# TubeBoard.net
KiCad netlist of a schematic drawn in EAGLE
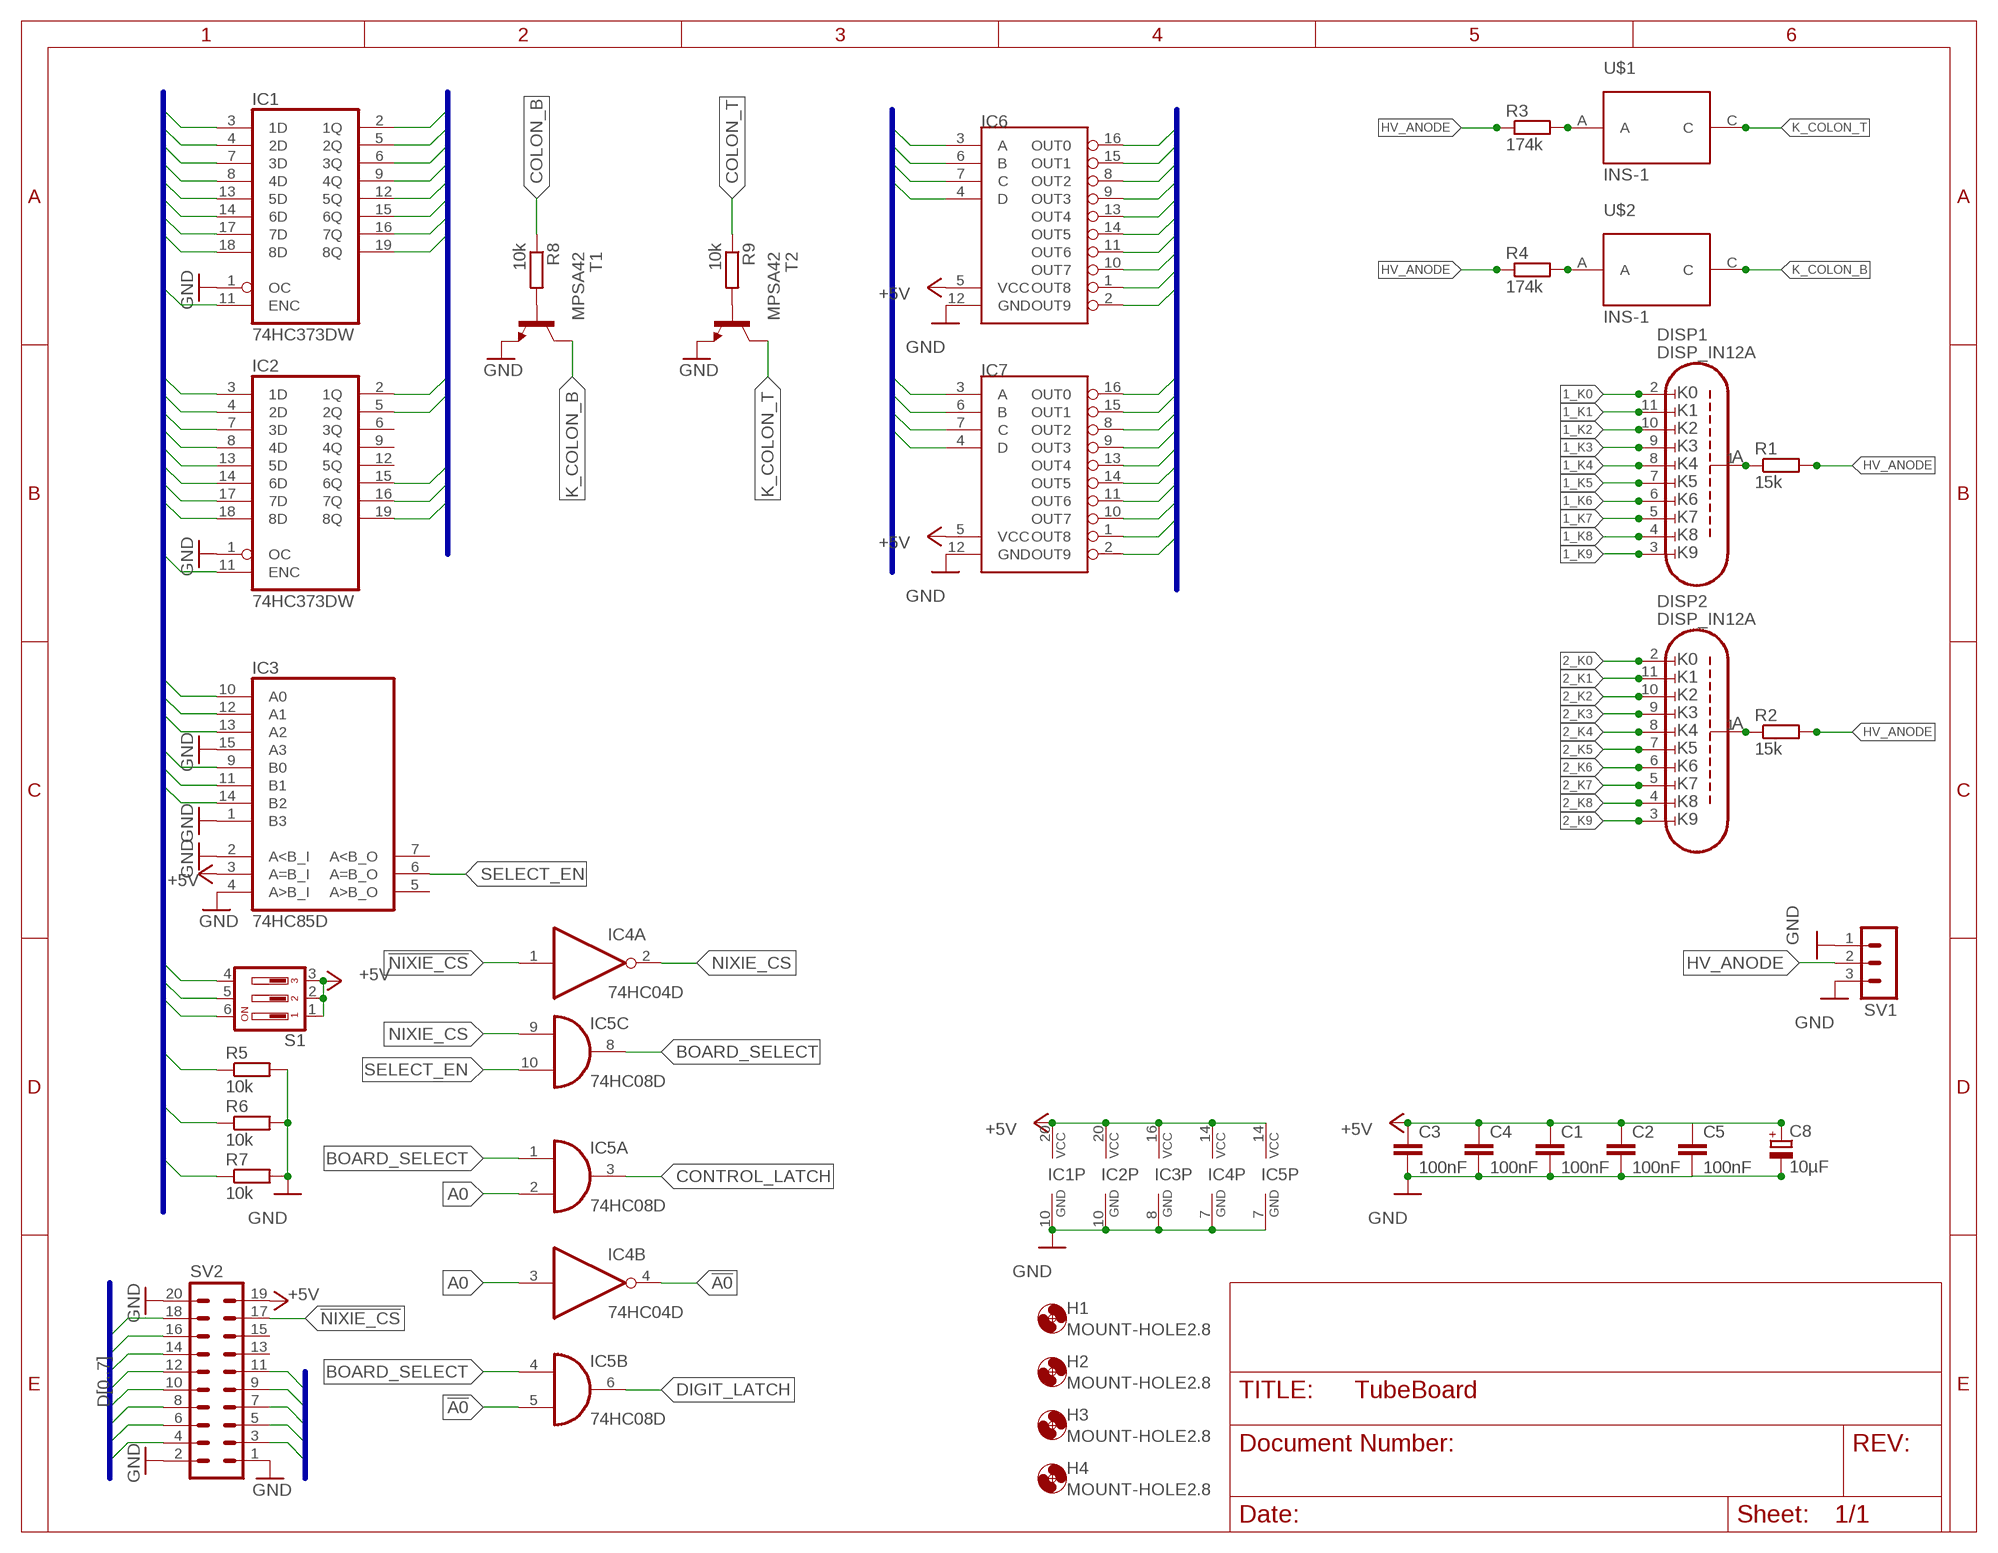
[diagram p0: schematic, sheet 1]

(export (version "E")
  (design (tool "Eeschema 10.0.6"))
  (components
    (comp (ref "C1")
      (value "100nF")
      (footprint "eagle-import:C1206")
      (libsource (lib "eagle-import") (part "C-EUC1206"))
    )
    (comp (ref "C2")
      (value "100nF")
      (footprint "eagle-import:C1206")
      (libsource (lib "eagle-import") (part "C-EUC1206"))
    )
    (comp (ref "C3")
      (value "100nF")
      (footprint "eagle-import:C1206")
      (libsource (lib "eagle-import") (part "C-EUC1206"))
    )
    (comp (ref "C4")
      (value "100nF")
      (footprint "eagle-import:C1206")
      (libsource (lib "eagle-import") (part "C-EUC1206"))
    )
    (comp (ref "C5")
      (value "100nF")
      (footprint "eagle-import:C1206")
      (libsource (lib "eagle-import") (part "C-EUC1206"))
    )
    (comp (ref "C8")
      (value "10µF")
      (footprint "eagle-import:SMC_B")
      (libsource (lib "eagle-import") (part "CPOL-EUSMCB"))
    )
    (comp (ref "DISP1")
      (value "DISP_IN12A")
      (footprint "eagle-import:DISP_IN-12_SOCKET")
      (libsource (lib "eagle-import") (part "DISP_IN12A"))
    )
    (comp (ref "DISP2")
      (value "DISP_IN12A")
      (footprint "eagle-import:DISP_IN-12_SOCKET")
      (libsource (lib "eagle-import") (part "DISP_IN12A"))
    )
    (comp (ref "H1")
      (value "MOUNT-HOLE2.8")
      (footprint "eagle-import:2,8")
      (libsource (lib "eagle-import") (part "MOUNT-HOLE2.8"))
    )
    (comp (ref "H2")
      (value "MOUNT-HOLE2.8")
      (footprint "eagle-import:2,8")
      (libsource (lib "eagle-import") (part "MOUNT-HOLE2.8"))
    )
    (comp (ref "H3")
      (value "MOUNT-HOLE2.8")
      (footprint "eagle-import:2,8")
      (libsource (lib "eagle-import") (part "MOUNT-HOLE2.8"))
    )
    (comp (ref "H4")
      (value "MOUNT-HOLE2.8")
      (footprint "eagle-import:2,8")
      (libsource (lib "eagle-import") (part "MOUNT-HOLE2.8"))
    )
    (comp (ref "IC1")
      (value "74HC373DW")
      (footprint "eagle-import:SO20W")
      (libsource (lib "eagle-import") (part "74373DWHC"))
    )
    (comp (ref "IC2")
      (value "74HC373DW")
      (footprint "eagle-import:SO20W")
      (libsource (lib "eagle-import") (part "74373DWHC"))
    )
    (comp (ref "IC3")
      (value "74HC85D")
      (footprint "eagle-import:SO16")
      (fields (field (name "MOUSER") "771-74HC85D-T"))
      (libsource (lib "eagle-import") (part "7485DHC"))
    )
    (comp (ref "IC4")
      (value "74HC04D")
      (footprint "eagle-import:SO14")
      (libsource (lib "eagle-import") (part "7404DHC"))
    )
    (comp (ref "IC5")
      (value "74HC08D")
      (footprint "eagle-import:SO14")
      (libsource (lib "eagle-import") (part "7408DHC"))
    )
    (comp (ref "IC6")
      (value "7441DIL16")
      (footprint "eagle-import:DIL16")
      (libsource (lib "eagle-import") (part "7441DIL16"))
    )
    (comp (ref "IC7")
      (value "7441DIL16")
      (footprint "eagle-import:DIL16")
      (libsource (lib "eagle-import") (part "7441DIL16"))
    )
    (comp (ref "R1")
      (value "15k")
      (footprint "eagle-import:0411_12")
      (libsource (lib "eagle-import") (part "R-EU_0411/12"))
    )
    (comp (ref "R2")
      (value "15k")
      (footprint "eagle-import:0411_12")
      (libsource (lib "eagle-import") (part "R-EU_0411/12"))
    )
    (comp (ref "R3")
      (value "174k")
      (footprint "eagle-import:M1206")
      (libsource (lib "eagle-import") (part "R-EU_M1206"))
    )
    (comp (ref "R4")
      (value "174k")
      (footprint "eagle-import:M1206")
      (libsource (lib "eagle-import") (part "R-EU_M1206"))
    )
    (comp (ref "R5")
      (value "10k")
      (footprint "eagle-import:R2012")
      (libsource (lib "eagle-import") (part "R-EU_R2012"))
    )
    (comp (ref "R6")
      (value "10k")
      (footprint "eagle-import:R2012")
      (libsource (lib "eagle-import") (part "R-EU_R2012"))
    )
    (comp (ref "R7")
      (value "10k")
      (footprint "eagle-import:R2012")
      (libsource (lib "eagle-import") (part "R-EU_R2012"))
    )
    (comp (ref "R8")
      (value "10k")
      (footprint "eagle-import:R2012")
      (libsource (lib "eagle-import") (part "R-EU_R2012"))
    )
    (comp (ref "R9")
      (value "10k")
      (footprint "eagle-import:R2012")
      (libsource (lib "eagle-import") (part "R-EU_R2012"))
    )
    (comp (ref "S1")
      (value "SD4-03")
      (footprint "eagle-import:SD4-03")
      (libsource (lib "eagle-import") (part "SD4-03"))
    )
    (comp (ref "SV1")
      (value "MA03-1")
      (footprint "eagle-import:MA03-1")
      (libsource (lib "eagle-import") (part "MA03-1"))
    )
    (comp (ref "SV2")
      (value "MA10-2")
      (footprint "eagle-import:MA10-2")
      (libsource (lib "eagle-import") (part "MA10-2"))
    )
    (comp (ref "T1")
      (value "MPSA42")
      (footprint "eagle-import:TO92-EBC")
      (libsource (lib "eagle-import") (part "-NPN-TO92-EBCMPSA42"))
    )
    (comp (ref "T2")
      (value "MPSA42")
      (footprint "eagle-import:TO92-EBC")
      (libsource (lib "eagle-import") (part "-NPN-TO92-EBCMPSA42"))
    )
    (comp (ref "U$1")
      (value "INS-1")
      (footprint "eagle-import:INS-1")
      (libsource (lib "eagle-import") (part "INS-1"))
    )
    (comp (ref "U$2")
      (value "INS-1")
      (footprint "eagle-import:INS-1")
      (libsource (lib "eagle-import") (part "INS-1"))
    )
  )
  (nets
    (net (code "1") (name "+5V") (class "Default")
      (node (ref "C1") (pin "1") (pinfunction "1_1") (pintype "passive"))
      (node (ref "C2") (pin "1") (pinfunction "1_1") (pintype "passive"))
      (node (ref "C3") (pin "1") (pinfunction "1_1") (pintype "passive"))
      (node (ref "C4") (pin "1") (pinfunction "1_1") (pintype "passive"))
      (node (ref "C5") (pin "1") (pinfunction "1_1") (pintype "passive"))
      (node (ref "C8") (pin "+") (pinfunction "+_+") (pintype "passive"))
      (node (ref "IC1") (pin "20") (pinfunction "VCC_20") (pintype "power_in"))
      (node (ref "IC2") (pin "20") (pinfunction "VCC_20") (pintype "power_in"))
      (node (ref "IC3") (pin "16") (pinfunction "VCC_16") (pintype "power_in"))
      (node (ref "IC3") (pin "3") (pinfunction "A=B_I_3") (pintype "input"))
      (node (ref "IC4") (pin "14") (pinfunction "VCC_14") (pintype "power_in"))
      (node (ref "IC5") (pin "14") (pinfunction "VCC_14") (pintype "power_in"))
      (node (ref "IC6") (pin "5") (pinfunction "VCC_5") (pintype "passive"))
      (node (ref "IC7") (pin "5") (pinfunction "VCC_5") (pintype "passive"))
      (node (ref "S1") (pin "1") (pinfunction "1_1") (pintype "passive"))
      (node (ref "S1") (pin "2") (pinfunction "2_2") (pintype "passive"))
      (node (ref "S1") (pin "3") (pinfunction "3_3") (pintype "passive"))
      (node (ref "SV2") (pin "19") (pinfunction "19_19") (pintype "passive"))
    )
    (net (code "2") (name "/A2") (class "Default")
      (node (ref "IC3") (pin "10") (pinfunction "A0_10") (pintype "input"))
      (node (ref "SV2") (pin "7") (pinfunction "7_7") (pintype "passive"))
    )
    (net (code "3") (name "/A3") (class "Default")
      (node (ref "IC3") (pin "12") (pinfunction "A1_12") (pintype "input"))
      (node (ref "SV2") (pin "9") (pinfunction "9_9") (pintype "passive"))
    )
    (net (code "4") (name "/A4") (class "Default")
      (node (ref "IC3") (pin "13") (pinfunction "A2_13") (pintype "input"))
      (node (ref "SV2") (pin "11") (pinfunction "11_11") (pintype "passive"))
    )
    (net (code "5") (name "/D0") (class "Default")
      (node (ref "IC1") (pin "3") (pinfunction "1D_3") (pintype "input"))
      (node (ref "IC2") (pin "3") (pinfunction "1D_3") (pintype "input"))
      (node (ref "SV2") (pin "8") (pinfunction "8_8") (pintype "passive"))
    )
    (net (code "6") (name "/D1") (class "Default")
      (node (ref "IC1") (pin "4") (pinfunction "2D_4") (pintype "input"))
      (node (ref "IC2") (pin "4") (pinfunction "2D_4") (pintype "input"))
      (node (ref "SV2") (pin "6") (pinfunction "6_6") (pintype "passive"))
    )
    (net (code "7") (name "/D2") (class "Default")
      (node (ref "IC1") (pin "7") (pinfunction "3D_7") (pintype "input"))
      (node (ref "IC2") (pin "7") (pinfunction "3D_7") (pintype "input"))
      (node (ref "SV2") (pin "4") (pinfunction "4_4") (pintype "passive"))
    )
    (net (code "8") (name "/D3") (class "Default")
      (node (ref "IC1") (pin "8") (pinfunction "4D_8") (pintype "input"))
      (node (ref "IC2") (pin "8") (pinfunction "4D_8") (pintype "input"))
      (node (ref "SV2") (pin "10") (pinfunction "10_10") (pintype "passive"))
    )
    (net (code "9") (name "/D4") (class "Default")
      (node (ref "IC1") (pin "13") (pinfunction "5D_13") (pintype "input"))
      (node (ref "IC2") (pin "13") (pinfunction "5D_13") (pintype "input"))
      (node (ref "SV2") (pin "12") (pinfunction "12_12") (pintype "passive"))
    )
    (net (code "10") (name "/D5") (class "Default")
      (node (ref "IC1") (pin "14") (pinfunction "6D_14") (pintype "input"))
      (node (ref "IC2") (pin "14") (pinfunction "6D_14") (pintype "input"))
      (node (ref "SV2") (pin "14") (pinfunction "14_14") (pintype "passive"))
    )
    (net (code "11") (name "/D6") (class "Default")
      (node (ref "IC1") (pin "17") (pinfunction "7D_17") (pintype "input"))
      (node (ref "IC2") (pin "17") (pinfunction "7D_17") (pintype "input"))
      (node (ref "SV2") (pin "16") (pinfunction "16_16") (pintype "passive"))
    )
    (net (code "12") (name "/D7") (class "Default")
      (node (ref "IC1") (pin "18") (pinfunction "8D_18") (pintype "input"))
      (node (ref "IC2") (pin "18") (pinfunction "8D_18") (pintype "input"))
      (node (ref "SV2") (pin "18") (pinfunction "18_18") (pintype "passive"))
    )
    (net (code "14") (name "/ID0") (class "Default")
      (node (ref "IC3") (pin "9") (pinfunction "B0_9") (pintype "input"))
      (node (ref "R7") (pin "1") (pinfunction "1_1") (pintype "passive"))
      (node (ref "S1") (pin "6") (pinfunction "6_6") (pintype "passive"))
    )
    (net (code "15") (name "/ID1") (class "Default")
      (node (ref "IC3") (pin "11") (pinfunction "B1_11") (pintype "input"))
      (node (ref "R6") (pin "1") (pinfunction "1_1") (pintype "passive"))
      (node (ref "S1") (pin "5") (pinfunction "5_5") (pintype "passive"))
    )
    (net (code "16") (name "/ID2") (class "Default")
      (node (ref "IC3") (pin "14") (pinfunction "B2_14") (pintype "input"))
      (node (ref "R5") (pin "1") (pinfunction "1_1") (pintype "passive"))
      (node (ref "S1") (pin "4") (pinfunction "4_4") (pintype "passive"))
    )
    (net (code "17") (name "/LDIGIT0") (class "Default")
      (node (ref "IC1") (pin "2") (pinfunction "1Q_2") (pintype "tri_state"))
      (node (ref "IC6") (pin "3") (pinfunction "A_3") (pintype "input"))
    )
    (net (code "18") (name "/LDIGIT1") (class "Default")
      (node (ref "IC1") (pin "5") (pinfunction "2Q_5") (pintype "tri_state"))
      (node (ref "IC6") (pin "6") (pinfunction "B_6") (pintype "input"))
    )
    (net (code "19") (name "/LDIGIT2") (class "Default")
      (node (ref "IC1") (pin "6") (pinfunction "3Q_6") (pintype "tri_state"))
      (node (ref "IC6") (pin "7") (pinfunction "C_7") (pintype "input"))
    )
    (net (code "20") (name "/LDIGIT3") (class "Default")
      (node (ref "IC1") (pin "9") (pinfunction "4Q_9") (pintype "tri_state"))
      (node (ref "IC6") (pin "4") (pinfunction "D_4") (pintype "input"))
    )
    (net (code "21") (name "/RDIGIT0") (class "Default")
      (node (ref "IC1") (pin "12") (pinfunction "5Q_12") (pintype "tri_state"))
      (node (ref "IC7") (pin "3") (pinfunction "A_3") (pintype "input"))
    )
    (net (code "22") (name "/RDIGIT1") (class "Default")
      (node (ref "IC1") (pin "15") (pinfunction "6Q_15") (pintype "tri_state"))
      (node (ref "IC7") (pin "6") (pinfunction "B_6") (pintype "input"))
    )
    (net (code "23") (name "/RDIGIT2") (class "Default")
      (node (ref "IC1") (pin "16") (pinfunction "7Q_16") (pintype "tri_state"))
      (node (ref "IC7") (pin "7") (pinfunction "C_7") (pintype "input"))
    )
    (net (code "24") (name "/RDIGIT3") (class "Default")
      (node (ref "IC1") (pin "19") (pinfunction "8Q_19") (pintype "tri_state"))
      (node (ref "IC7") (pin "4") (pinfunction "D_4") (pintype "input"))
    )
    (net (code "25") (name "/~{A0}") (class "Default")
      (node (ref "IC4") (pin "4") (pinfunction "O_4") (pintype "output"))
      (node (ref "IC5") (pin "5") (pinfunction "I1_5") (pintype "input"))
    )
    (net (code "26") (name "/~{NIXIE_CS}") (class "Default")
      (node (ref "IC4") (pin "1") (pinfunction "I_1") (pintype "input"))
      (node (ref "SV2") (pin "17") (pinfunction "17_17") (pintype "passive"))
    )
    (net (code "27") (name "1_K0") (class "Default")
      (node (ref "DISP1") (pin "2") (pinfunction "K0_2") (pintype "input"))
      (node (ref "IC6") (pin "16") (pinfunction "OUT0_16") (pintype "output"))
    )
    (net (code "28") (name "1_K1") (class "Default")
      (node (ref "DISP1") (pin "11") (pinfunction "K1_11") (pintype "input"))
      (node (ref "IC6") (pin "15") (pinfunction "OUT1_15") (pintype "output"))
    )
    (net (code "29") (name "1_K2") (class "Default")
      (node (ref "DISP1") (pin "10") (pinfunction "K2_10") (pintype "input"))
      (node (ref "IC6") (pin "8") (pinfunction "OUT2_8") (pintype "output"))
    )
    (net (code "30") (name "1_K3") (class "Default")
      (node (ref "DISP1") (pin "9") (pinfunction "K3_9") (pintype "input"))
      (node (ref "IC6") (pin "9") (pinfunction "OUT3_9") (pintype "output"))
    )
    (net (code "31") (name "1_K4") (class "Default")
      (node (ref "DISP1") (pin "8") (pinfunction "K4_8") (pintype "input"))
      (node (ref "IC6") (pin "13") (pinfunction "OUT4_13") (pintype "output"))
    )
    (net (code "32") (name "1_K5") (class "Default")
      (node (ref "DISP1") (pin "7") (pinfunction "K5_7") (pintype "input"))
      (node (ref "IC6") (pin "14") (pinfunction "OUT5_14") (pintype "output"))
    )
    (net (code "33") (name "1_K6") (class "Default")
      (node (ref "DISP1") (pin "6") (pinfunction "K6_6") (pintype "input"))
      (node (ref "IC6") (pin "11") (pinfunction "OUT6_11") (pintype "output"))
    )
    (net (code "34") (name "1_K7") (class "Default")
      (node (ref "DISP1") (pin "5") (pinfunction "K7_5") (pintype "input"))
      (node (ref "IC6") (pin "10") (pinfunction "OUT7_10") (pintype "output"))
    )
    (net (code "35") (name "1_K8") (class "Default")
      (node (ref "DISP1") (pin "4") (pinfunction "K8_4") (pintype "input"))
      (node (ref "IC6") (pin "1") (pinfunction "OUT8_1") (pintype "output"))
    )
    (net (code "36") (name "1_K9") (class "Default")
      (node (ref "DISP1") (pin "3") (pinfunction "K9_3") (pintype "input"))
      (node (ref "IC6") (pin "2") (pinfunction "OUT9_2") (pintype "output"))
    )
    (net (code "37") (name "2_K0") (class "Default")
      (node (ref "DISP2") (pin "2") (pinfunction "K0_2") (pintype "input"))
      (node (ref "IC7") (pin "16") (pinfunction "OUT0_16") (pintype "output"))
    )
    (net (code "38") (name "2_K1") (class "Default")
      (node (ref "DISP2") (pin "11") (pinfunction "K1_11") (pintype "input"))
      (node (ref "IC7") (pin "15") (pinfunction "OUT1_15") (pintype "output"))
    )
    (net (code "39") (name "2_K2") (class "Default")
      (node (ref "DISP2") (pin "10") (pinfunction "K2_10") (pintype "input"))
      (node (ref "IC7") (pin "8") (pinfunction "OUT2_8") (pintype "output"))
    )
    (net (code "40") (name "2_K3") (class "Default")
      (node (ref "DISP2") (pin "9") (pinfunction "K3_9") (pintype "input"))
      (node (ref "IC7") (pin "9") (pinfunction "OUT3_9") (pintype "output"))
    )
    (net (code "41") (name "2_K4") (class "Default")
      (node (ref "DISP2") (pin "8") (pinfunction "K4_8") (pintype "input"))
      (node (ref "IC7") (pin "13") (pinfunction "OUT4_13") (pintype "output"))
    )
    (net (code "42") (name "2_K5") (class "Default")
      (node (ref "DISP2") (pin "7") (pinfunction "K5_7") (pintype "input"))
      (node (ref "IC7") (pin "14") (pinfunction "OUT5_14") (pintype "output"))
    )
    (net (code "43") (name "2_K6") (class "Default")
      (node (ref "DISP2") (pin "6") (pinfunction "K6_6") (pintype "input"))
      (node (ref "IC7") (pin "11") (pinfunction "OUT6_11") (pintype "output"))
    )
    (net (code "44") (name "2_K7") (class "Default")
      (node (ref "DISP2") (pin "5") (pinfunction "K7_5") (pintype "input"))
      (node (ref "IC7") (pin "10") (pinfunction "OUT7_10") (pintype "output"))
    )
    (net (code "45") (name "2_K8") (class "Default")
      (node (ref "DISP2") (pin "4") (pinfunction "K8_4") (pintype "input"))
      (node (ref "IC7") (pin "1") (pinfunction "OUT8_1") (pintype "output"))
    )
    (net (code "46") (name "2_K9") (class "Default")
      (node (ref "DISP2") (pin "3") (pinfunction "K9_3") (pintype "input"))
      (node (ref "IC7") (pin "2") (pinfunction "OUT9_2") (pintype "output"))
    )
    (net (code "47") (name "A0") (class "Default")
      (node (ref "IC4") (pin "3") (pinfunction "I_3") (pintype "input"))
      (node (ref "IC5") (pin "2") (pinfunction "I1_2") (pintype "input"))
      (node (ref "SV2") (pin "3") (pinfunction "3_3") (pintype "passive"))
    )
    (net (code "48") (name "BOARD_SELECT") (class "Default")
      (node (ref "IC5") (pin "1") (pinfunction "I0_1") (pintype "input"))
      (node (ref "IC5") (pin "4") (pinfunction "I0_4") (pintype "input"))
      (node (ref "IC5") (pin "8") (pinfunction "O_8") (pintype "output"))
    )
    (net (code "49") (name "COLON_B") (class "Default")
      (node (ref "IC2") (pin "2") (pinfunction "1Q_2") (pintype "tri_state"))
      (node (ref "R8") (pin "1") (pinfunction "1_1") (pintype "passive"))
    )
    (net (code "50") (name "COLON_T") (class "Default")
      (node (ref "IC2") (pin "5") (pinfunction "2Q_5") (pintype "tri_state"))
      (node (ref "R9") (pin "1") (pinfunction "1_1") (pintype "passive"))
    )
    (net (code "51") (name "CONTROL_LATCH") (class "Default")
      (node (ref "IC2") (pin "11") (pinfunction "ENC_11") (pintype "input"))
      (node (ref "IC5") (pin "3") (pinfunction "O_3") (pintype "output"))
    )
    (net (code "52") (name "DIGIT_LATCH") (class "Default")
      (node (ref "IC1") (pin "11") (pinfunction "ENC_11") (pintype "input"))
      (node (ref "IC5") (pin "6") (pinfunction "O_6") (pintype "output"))
    )
    (net (code "53") (name "GND") (class "Default")
      (node (ref "C1") (pin "2") (pinfunction "2_2") (pintype "passive"))
      (node (ref "C2") (pin "2") (pinfunction "2_2") (pintype "passive"))
      (node (ref "C3") (pin "2") (pinfunction "2_2") (pintype "passive"))
      (node (ref "C4") (pin "2") (pinfunction "2_2") (pintype "passive"))
      (node (ref "C5") (pin "2") (pinfunction "2_2") (pintype "passive"))
      (node (ref "C8") (pin "-") (pinfunction "-_-") (pintype "passive"))
      (node (ref "IC1") (pin "1") (pinfunction "OC_1") (pintype "input"))
      (node (ref "IC1") (pin "10") (pinfunction "GND_10") (pintype "power_in"))
      (node (ref "IC2") (pin "1") (pinfunction "OC_1") (pintype "input"))
      (node (ref "IC2") (pin "10") (pinfunction "GND_10") (pintype "power_in"))
      (node (ref "IC3") (pin "1") (pinfunction "B3_1") (pintype "input"))
      (node (ref "IC3") (pin "15") (pinfunction "A3_15") (pintype "input"))
      (node (ref "IC3") (pin "2") (pinfunction "A<B_I_2") (pintype "input"))
      (node (ref "IC3") (pin "4") (pinfunction "A>B_I_4") (pintype "input"))
      (node (ref "IC3") (pin "8") (pinfunction "GND_8") (pintype "power_in"))
      (node (ref "IC4") (pin "7") (pinfunction "GND_7") (pintype "power_in"))
      (node (ref "IC5") (pin "7") (pinfunction "GND_7") (pintype "power_in"))
      (node (ref "IC6") (pin "12") (pinfunction "GND_12") (pintype "passive"))
      (node (ref "IC7") (pin "12") (pinfunction "GND_12") (pintype "passive"))
      (node (ref "R5") (pin "2") (pinfunction "2_2") (pintype "passive"))
      (node (ref "R6") (pin "2") (pinfunction "2_2") (pintype "passive"))
      (node (ref "R7") (pin "2") (pinfunction "2_2") (pintype "passive"))
      (node (ref "SV1") (pin "1") (pinfunction "1_1") (pintype "passive"))
      (node (ref "SV1") (pin "3") (pinfunction "3_3") (pintype "passive"))
      (node (ref "SV2") (pin "1") (pinfunction "1_1") (pintype "passive"))
      (node (ref "SV2") (pin "2") (pinfunction "2_2") (pintype "passive"))
      (node (ref "SV2") (pin "20") (pinfunction "20_20") (pintype "passive"))
      (node (ref "T1") (pin "E") (pinfunction "E_E") (pintype "passive"))
      (node (ref "T2") (pin "E") (pinfunction "E_E") (pintype "passive"))
    )
    (net (code "54") (name "HV_ANODE") (class "Default")
      (node (ref "R1") (pin "2") (pinfunction "2_2") (pintype "passive"))
      (node (ref "R2") (pin "2") (pinfunction "2_2") (pintype "passive"))
      (node (ref "R3") (pin "1") (pinfunction "1_1") (pintype "passive"))
      (node (ref "R4") (pin "1") (pinfunction "1_1") (pintype "passive"))
      (node (ref "SV1") (pin "2") (pinfunction "2_2") (pintype "passive"))
    )
    (net (code "55") (name "K_COLON_B") (class "Default")
      (node (ref "T1") (pin "C") (pinfunction "C_C") (pintype "passive"))
      (node (ref "U$2") (pin "C") (pinfunction "C_C") (pintype "bidirectional"))
    )
    (net (code "56") (name "K_COLON_T") (class "Default")
      (node (ref "T2") (pin "C") (pinfunction "C_C") (pintype "passive"))
      (node (ref "U$1") (pin "C") (pinfunction "C_C") (pintype "bidirectional"))
    )
    (net (code "57") (name "NIXIE_CS") (class "Default")
      (node (ref "IC4") (pin "2") (pinfunction "O_2") (pintype "output"))
      (node (ref "IC5") (pin "9") (pinfunction "I0_9") (pintype "input"))
    )
    (net (code "58") (name "Net-(DISP1-ANODE)") (class "Default")
      (node (ref "DISP1") (pin "1") (pinfunction "ANODE_1") (pintype "input"))
      (node (ref "R1") (pin "1") (pinfunction "1_1") (pintype "passive"))
    )
    (net (code "59") (name "Net-(DISP2-ANODE)") (class "Default")
      (node (ref "DISP2") (pin "1") (pinfunction "ANODE_1") (pintype "input"))
      (node (ref "R2") (pin "1") (pinfunction "1_1") (pintype "passive"))
    )
    (net (code "60") (name "Net-(R3-Pad2)") (class "Default")
      (node (ref "R3") (pin "2") (pinfunction "2_2") (pintype "passive"))
      (node (ref "U$1") (pin "A") (pinfunction "A_A") (pintype "bidirectional"))
    )
    (net (code "61") (name "Net-(R4-Pad2)") (class "Default")
      (node (ref "R4") (pin "2") (pinfunction "2_2") (pintype "passive"))
      (node (ref "U$2") (pin "A") (pinfunction "A_A") (pintype "bidirectional"))
    )
    (net (code "62") (name "Net-(R8-Pad2)") (class "Default")
      (node (ref "R8") (pin "2") (pinfunction "2_2") (pintype "passive"))
      (node (ref "T1") (pin "B") (pinfunction "B_B") (pintype "passive"))
    )
    (net (code "63") (name "Net-(R9-Pad2)") (class "Default")
      (node (ref "R9") (pin "2") (pinfunction "2_2") (pintype "passive"))
      (node (ref "T2") (pin "B") (pinfunction "B_B") (pintype "passive"))
    )
    (net (code "64") (name "SELECT_EN") (class "Default")
      (node (ref "IC3") (pin "6") (pinfunction "A=B_O_6") (pintype "output"))
      (node (ref "IC5") (pin "10") (pinfunction "I1_10") (pintype "input"))
    )
    (net (code "65") (name "unconnected-(IC2A-3Q-Pad6)") (class "Default")
      (node (ref "IC2") (pin "6") (pinfunction "3Q_6") (pintype "tri_state"))
    )
    (net (code "66") (name "unconnected-(IC2A-4Q-Pad9)") (class "Default")
      (node (ref "IC2") (pin "9") (pinfunction "4Q_9") (pintype "tri_state"))
    )
    (net (code "67") (name "unconnected-(IC2A-5Q-Pad12)") (class "Default")
      (node (ref "IC2") (pin "12") (pinfunction "5Q_12") (pintype "tri_state"))
    )
    (net (code "68") (name "unconnected-(IC2A-6Q-Pad15)") (class "Default")
      (node (ref "IC2") (pin "15") (pinfunction "6Q_15") (pintype "tri_state"))
    )
    (net (code "69") (name "unconnected-(IC2A-7Q-Pad16)") (class "Default")
      (node (ref "IC2") (pin "16") (pinfunction "7Q_16") (pintype "tri_state"))
    )
    (net (code "70") (name "unconnected-(IC2A-8Q-Pad19)") (class "Default")
      (node (ref "IC2") (pin "19") (pinfunction "8Q_19") (pintype "tri_state"))
    )
    (net (code "71") (name "unconnected-(IC3A-A<B_O-Pad7)") (class "Default")
      (node (ref "IC3") (pin "7") (pinfunction "A<B_O_7") (pintype "output"))
    )
    (net (code "72") (name "unconnected-(IC3A-A>B_O-Pad5)") (class "Default")
      (node (ref "IC3") (pin "5") (pinfunction "A>B_O_5") (pintype "output"))
    )
    (net (code "73") (name "unconnected-(SV2-Pad5)") (class "Default")
      (node (ref "SV2") (pin "5") (pinfunction "5_5") (pintype "passive"))
    )
    (net (code "74") (name "unconnected-(SV2-Pad13)") (class "Default")
      (node (ref "SV2") (pin "13") (pinfunction "13_13") (pintype "passive"))
    )
    (net (code "75") (name "unconnected-(SV2-Pad15)") (class "Default")
      (node (ref "SV2") (pin "15") (pinfunction "15_15") (pintype "passive"))
    )
  )
)
